# DUAL_POWER_SUPPLY.net
KiCad netlist of a schematic drawn in EAGLE
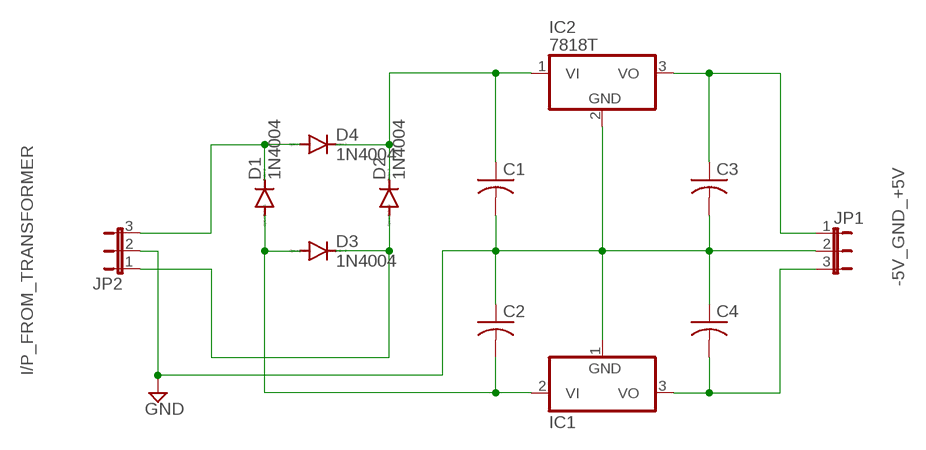
[diagram p0: schematic, sheet 1]

(export (version "E")
  (design (tool "Eeschema 10.0.6"))
  (components
    (comp (ref "C1")
      (value "C-US025-024X044")
      (footprint "eagle-import:C025-024X044")
      (libsource (lib "eagle-import") (part "C-US025-024X044"))
    )
    (comp (ref "C2")
      (value "C-US025-024X044")
      (footprint "eagle-import:C025-024X044")
      (libsource (lib "eagle-import") (part "C-US025-024X044"))
    )
    (comp (ref "C3")
      (value "C-US025-024X044")
      (footprint "eagle-import:C025-024X044")
      (libsource (lib "eagle-import") (part "C-US025-024X044"))
    )
    (comp (ref "C4")
      (value "C-US025-024X044")
      (footprint "eagle-import:C025-024X044")
      (libsource (lib "eagle-import") (part "C-US025-024X044"))
    )
    (comp (ref "D1")
      (value "1N4004")
      (footprint "eagle-import:DO41-10")
      (libsource (lib "eagle-import") (part "1N4004"))
    )
    (comp (ref "D2")
      (value "1N4004")
      (footprint "eagle-import:DO41-10")
      (libsource (lib "eagle-import") (part "1N4004"))
    )
    (comp (ref "D3")
      (value "1N4004")
      (footprint "eagle-import:DO41-10")
      (libsource (lib "eagle-import") (part "1N4004"))
    )
    (comp (ref "D4")
      (value "1N4004")
      (footprint "eagle-import:DO41-10")
      (libsource (lib "eagle-import") (part "1N4004"))
    )
    (comp (ref "IC1")
      (value "79L05Z")
      (footprint "eagle-import:TO92")
      (libsource (lib "eagle-import") (part "79ZL05"))
    )
    (comp (ref "IC2")
      (value "7818T")
      (footprint "eagle-import:TO220H")
      (libsource (lib "eagle-import") (part "78T18"))
    )
    (comp (ref "JP1")
      (value "JP2E")
      (footprint "eagle-import:JP2")
      (libsource (lib "eagle-import") (part "JP2E"))
    )
    (comp (ref "JP2")
      (value "JP2E")
      (footprint "eagle-import:JP2")
      (libsource (lib "eagle-import") (part "JP2E"))
    )
  )
  (nets
    (net (code "1") (name "GND") (class "Default")
      (node (ref "C1") (pin "2") (pinfunction "2_2") (pintype "passive"))
      (node (ref "C2") (pin "1") (pinfunction "1_1") (pintype "passive"))
      (node (ref "C3") (pin "2") (pinfunction "2_2") (pintype "passive"))
      (node (ref "C4") (pin "1") (pinfunction "1_1") (pintype "passive"))
      (node (ref "IC1") (pin "1") (pinfunction "GND_1") (pintype "passive"))
      (node (ref "IC2") (pin "2") (pinfunction "GND_2") (pintype "passive"))
      (node (ref "JP1") (pin "2") (pinfunction "2_2") (pintype "passive"))
      (node (ref "JP2") (pin "2") (pinfunction "2_2") (pintype "passive"))
    )
    (net (code "2") (name "Net-(D1-PadC)") (class "Default")
      (node (ref "D1") (pin "C") (pinfunction "C_C") (pintype "passive"))
      (node (ref "D4") (pin "A") (pinfunction "A_A") (pintype "passive"))
      (node (ref "JP2") (pin "3") (pinfunction "3_3") (pintype "passive"))
    )
    (net (code "3") (name "Net-(D2-PadA)") (class "Default")
      (node (ref "D2") (pin "A") (pinfunction "A_A") (pintype "passive"))
      (node (ref "D3") (pin "C") (pinfunction "C_C") (pintype "passive"))
      (node (ref "JP2") (pin "1") (pinfunction "1_1") (pintype "passive"))
    )
    (net (code "4") (name "Net-(IC1-VI)") (class "Default")
      (node (ref "C2") (pin "2") (pinfunction "2_2") (pintype "passive"))
      (node (ref "D1") (pin "A") (pinfunction "A_A") (pintype "passive"))
      (node (ref "D3") (pin "A") (pinfunction "A_A") (pintype "passive"))
      (node (ref "IC1") (pin "2") (pinfunction "VI_2") (pintype "input"))
    )
    (net (code "5") (name "Net-(IC1-VO)") (class "Default")
      (node (ref "C4") (pin "2") (pinfunction "2_2") (pintype "passive"))
      (node (ref "IC1") (pin "3") (pinfunction "VO_3") (pintype "passive"))
      (node (ref "JP1") (pin "3") (pinfunction "3_3") (pintype "passive"))
    )
    (net (code "6") (name "Net-(IC2-VI)") (class "Default")
      (node (ref "C1") (pin "1") (pinfunction "1_1") (pintype "passive"))
      (node (ref "D2") (pin "C") (pinfunction "C_C") (pintype "passive"))
      (node (ref "D4") (pin "C") (pinfunction "C_C") (pintype "passive"))
      (node (ref "IC2") (pin "1") (pinfunction "VI_1") (pintype "input"))
    )
    (net (code "7") (name "Net-(IC2-VO)") (class "Default")
      (node (ref "C3") (pin "1") (pinfunction "1_1") (pintype "passive"))
      (node (ref "IC2") (pin "3") (pinfunction "VO_3") (pintype "passive"))
      (node (ref "JP1") (pin "1") (pinfunction "1_1") (pintype "passive"))
    )
  )
)
